# NFC-Attendance-System.net
KiCad netlist of a schematic drawn in EAGLE
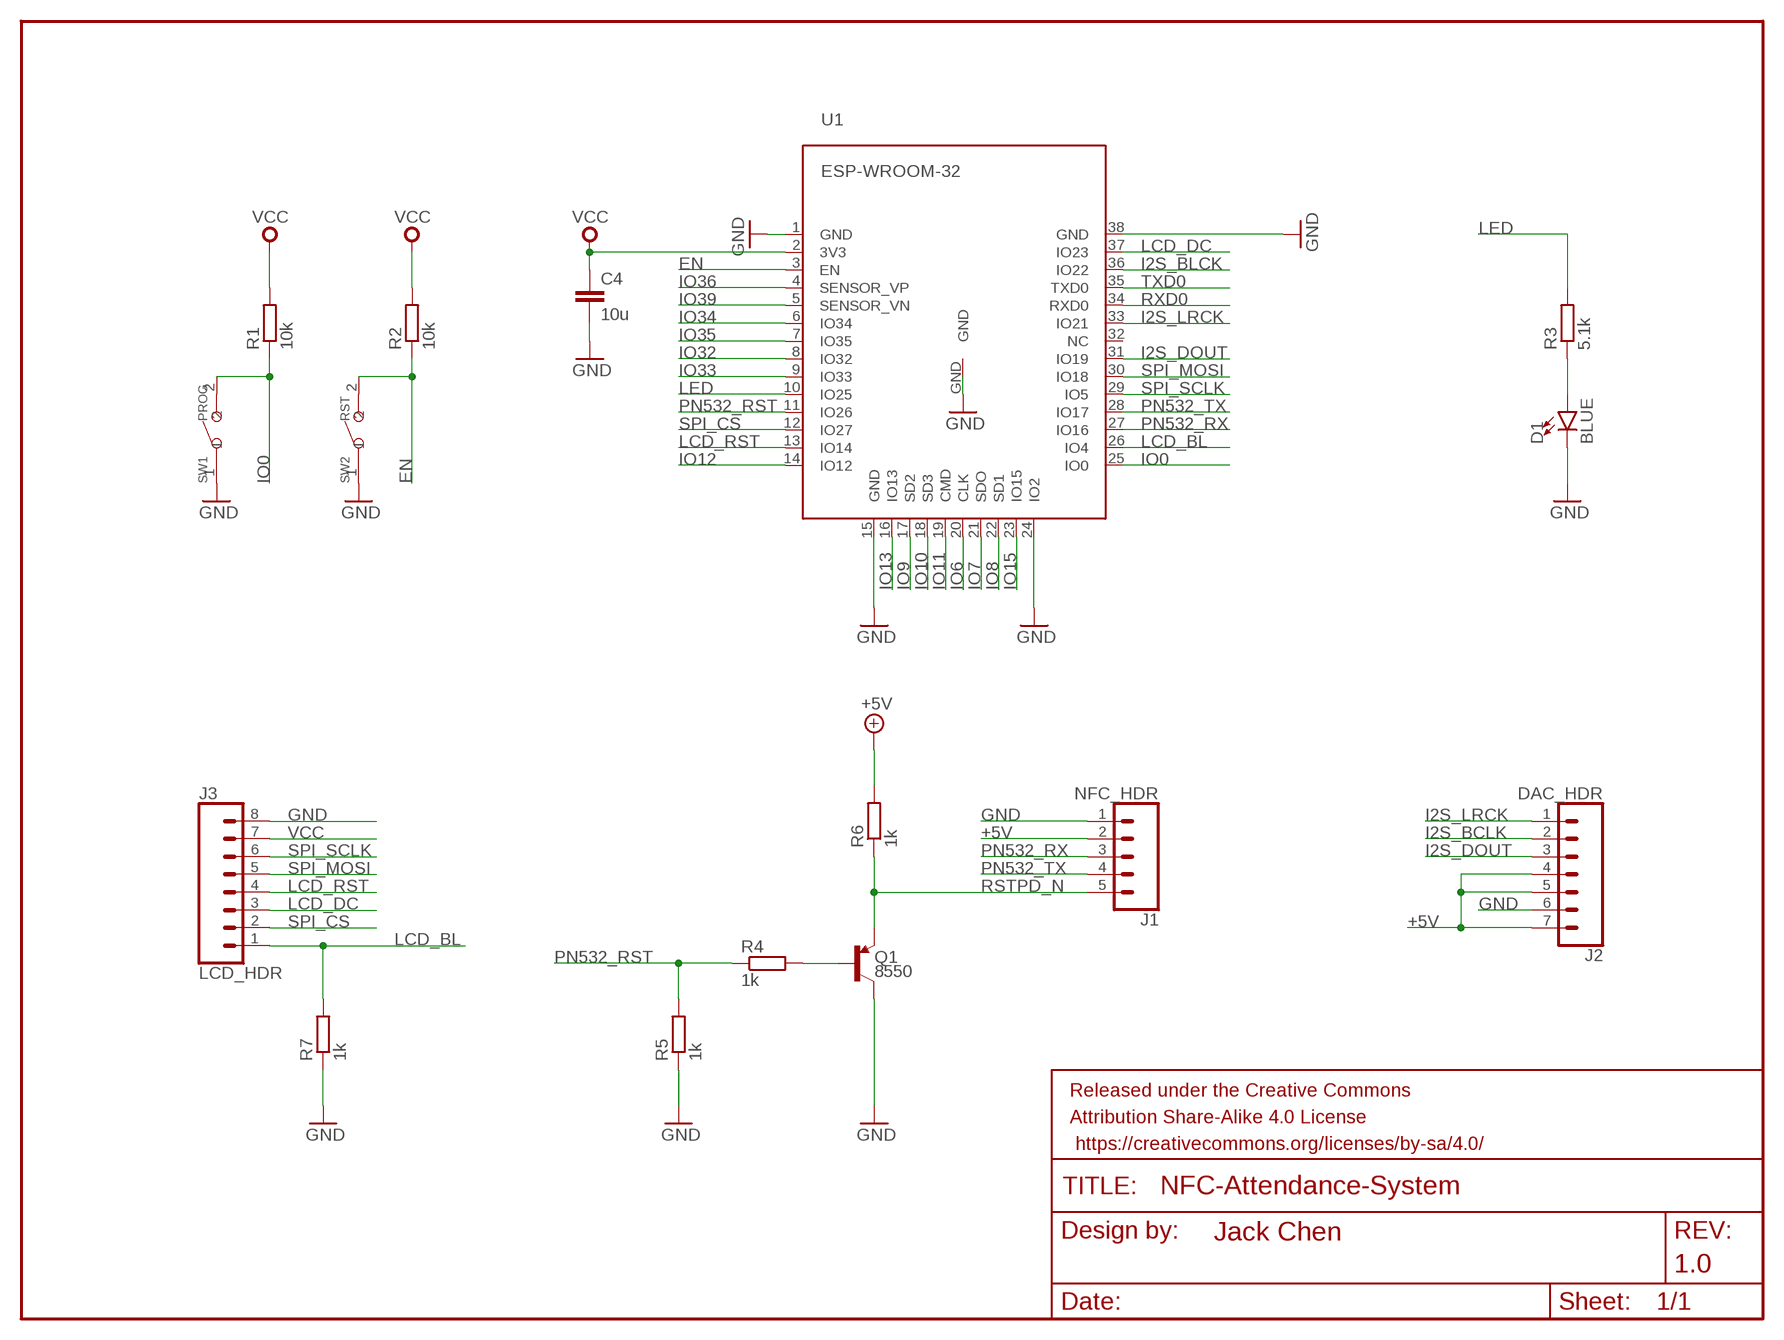
[diagram p0: schematic, sheet 1]

(export (version "E")
  (design (tool "Eeschema 10.0.6"))
  (components
    (comp (ref "C4")
      (value "10u")
      (footprint "eagle-import:C0603")
      (libsource (lib "eagle-import") (part "C-EUC0603"))
    )
    (comp (ref "D1")
      (value "BLUE")
      (footprint "eagle-import:LED_5MM")
      (libsource (lib "eagle-import") (part "LED5MM"))
    )
    (comp (ref "FRAME1")
      (value "FRAME-LETTER")
      (footprint "eagle-import:CREATIVE_COMMONS")
      (fields (field (name "DESIGNER") "Jack Chen") (field (name "REV") "1.0"))
      (libsource (lib "eagle-import") (part "FRAME-LETTER"))
    )
    (comp (ref "J1")
      (value "NFC_HDR")
      (footprint "eagle-import:1X05")
      (libsource (lib "eagle-import") (part "CONN_05"))
    )
    (comp (ref "J2")
      (value "DAC_HDR")
      (footprint "eagle-import:1X07")
      (libsource (lib "eagle-import") (part "CONN_07"))
    )
    (comp (ref "J3")
      (value "LCD_HDR")
      (footprint "eagle-import:1X08")
      (libsource (lib "eagle-import") (part "CONN_08{dblquote}"))
    )
    (comp (ref "Q1")
      (value "8550")
      (footprint "eagle-import:SOT23-3")
      (libsource (lib "eagle-import") (part "TRANS_PNP-MMBT4403"))
    )
    (comp (ref "R1")
      (value "10k")
      (footprint "eagle-import:R0603")
      (libsource (lib "eagle-import") (part "R-EU_R0603"))
    )
    (comp (ref "R2")
      (value "10k")
      (footprint "eagle-import:R0603")
      (libsource (lib "eagle-import") (part "R-EU_R0603"))
    )
    (comp (ref "R3")
      (value "5.1k")
      (footprint "eagle-import:R0603")
      (libsource (lib "eagle-import") (part "R-EU_R0603"))
    )
    (comp (ref "R4")
      (value "1k")
      (footprint "eagle-import:R0603")
      (libsource (lib "eagle-import") (part "R-EU_R0603"))
    )
    (comp (ref "R5")
      (value "1k")
      (footprint "eagle-import:R0603")
      (libsource (lib "eagle-import") (part "R-EU_R0603"))
    )
    (comp (ref "R6")
      (value "1k")
      (footprint "eagle-import:R0603")
      (libsource (lib "eagle-import") (part "R-EU_R0603"))
    )
    (comp (ref "R7")
      (value "1k")
      (footprint "eagle-import:R0603")
      (libsource (lib "eagle-import") (part "R-EU_R0603"))
    )
    (comp (ref "SW1")
      (value "PROG")
      (footprint "eagle-import:SW2-4.0-6.0X3.0X2.5MM")
      (libsource (lib "eagle-import") (part "SMD-BUTTON(2P-6.0X3.0X2.5MM)-DHT-1163S"))
    )
    (comp (ref "SW2")
      (value "RST")
      (footprint "eagle-import:SW2-4.0-6.0X3.0X2.5MM")
      (libsource (lib "eagle-import") (part "SMD-BUTTON(2P-6.0X3.0X2.5MM)-DHT-1163S"))
    )
    (comp (ref "U1")
      (value "ESP-WROOM-32")
      (footprint "eagle-import:ESP-WROOM-32")
      (libsource (lib "eagle-import") (part "ESP-WROOM-32"))
    )
  )
  (nets
    (net (code "1") (name "+5V") (class "Default")
      (node (ref "J1") (pin "2") (pinfunction "2_2") (pintype "passive"))
      (node (ref "J2") (pin "4") (pinfunction "4_4") (pintype "passive"))
      (node (ref "J2") (pin "5") (pinfunction "5_5") (pintype "passive"))
      (node (ref "J2") (pin "7") (pinfunction "7_7") (pintype "passive"))
      (node (ref "R6") (pin "2") (pinfunction "2_2") (pintype "passive"))
    )
    (net (code "2") (name "/EN") (class "Default")
      (node (ref "R2") (pin "1") (pinfunction "1_1") (pintype "passive"))
      (node (ref "SW2") (pin "2") (pinfunction "2_2") (pintype "bidirectional"))
      (node (ref "U1") (pin "3") (pinfunction "EN_3") (pintype "bidirectional"))
    )
    (net (code "3") (name "/I2S_BCLK") (class "Default")
      (node (ref "J2") (pin "2") (pinfunction "2_2") (pintype "passive"))
    )
    (net (code "4") (name "/I2S_BLCK") (class "Default")
      (node (ref "U1") (pin "36") (pinfunction "IO22_36") (pintype "bidirectional"))
    )
    (net (code "5") (name "/I2S_DOUT") (class "Default")
      (node (ref "J2") (pin "3") (pinfunction "3_3") (pintype "passive"))
      (node (ref "U1") (pin "31") (pinfunction "IO19_31") (pintype "bidirectional"))
    )
    (net (code "6") (name "/I2S_LRCK") (class "Default")
      (node (ref "J2") (pin "1") (pinfunction "1_1") (pintype "passive"))
      (node (ref "U1") (pin "33") (pinfunction "IO21_33") (pintype "bidirectional"))
    )
    (net (code "7") (name "/IO0") (class "Default")
      (node (ref "R1") (pin "1") (pinfunction "1_1") (pintype "passive"))
      (node (ref "SW1") (pin "2") (pinfunction "2_2") (pintype "bidirectional"))
      (node (ref "U1") (pin "25") (pinfunction "IO0_25") (pintype "bidirectional"))
    )
    (net (code "8") (name "/IO6") (class "Default")
      (node (ref "U1") (pin "20") (pinfunction "CLK_20") (pintype "bidirectional"))
    )
    (net (code "9") (name "/IO7") (class "Default")
      (node (ref "U1") (pin "21") (pinfunction "SDO_21") (pintype "bidirectional"))
    )
    (net (code "10") (name "/IO8") (class "Default")
      (node (ref "U1") (pin "22") (pinfunction "SD1_22") (pintype "bidirectional"))
    )
    (net (code "11") (name "/IO9") (class "Default")
      (node (ref "U1") (pin "17") (pinfunction "SD2_17") (pintype "bidirectional"))
    )
    (net (code "12") (name "/IO10") (class "Default")
      (node (ref "U1") (pin "18") (pinfunction "SD3_18") (pintype "bidirectional"))
    )
    (net (code "13") (name "/IO11") (class "Default")
      (node (ref "U1") (pin "19") (pinfunction "CMD_19") (pintype "bidirectional"))
    )
    (net (code "14") (name "/IO12") (class "Default")
      (node (ref "U1") (pin "14") (pinfunction "IO12_14") (pintype "bidirectional"))
    )
    (net (code "15") (name "/IO13") (class "Default")
      (node (ref "U1") (pin "16") (pinfunction "IO13_16") (pintype "bidirectional"))
    )
    (net (code "16") (name "/IO15") (class "Default")
      (node (ref "U1") (pin "23") (pinfunction "IO15_23") (pintype "bidirectional"))
    )
    (net (code "17") (name "/IO32") (class "Default")
      (node (ref "U1") (pin "8") (pinfunction "IO32_8") (pintype "bidirectional"))
    )
    (net (code "18") (name "/IO33") (class "Default")
      (node (ref "U1") (pin "9") (pinfunction "IO33_9") (pintype "bidirectional"))
    )
    (net (code "19") (name "/IO34") (class "Default")
      (node (ref "U1") (pin "6") (pinfunction "IO34_6") (pintype "bidirectional"))
    )
    (net (code "20") (name "/IO35") (class "Default")
      (node (ref "U1") (pin "7") (pinfunction "IO35_7") (pintype "bidirectional"))
    )
    (net (code "21") (name "/IO36") (class "Default")
      (node (ref "U1") (pin "4") (pinfunction "SENSOR_VP_4") (pintype "bidirectional"))
    )
    (net (code "22") (name "/IO39") (class "Default")
      (node (ref "U1") (pin "5") (pinfunction "SENSOR_VN_5") (pintype "bidirectional"))
    )
    (net (code "23") (name "/LCD_BL") (class "Default")
      (node (ref "J3") (pin "1") (pinfunction "1_1") (pintype "passive"))
      (node (ref "R7") (pin "2") (pinfunction "2_2") (pintype "passive"))
      (node (ref "U1") (pin "26") (pinfunction "IO4_26") (pintype "bidirectional"))
    )
    (net (code "24") (name "/LCD_DC") (class "Default")
      (node (ref "J3") (pin "3") (pinfunction "3_3") (pintype "passive"))
      (node (ref "U1") (pin "37") (pinfunction "IO23_37") (pintype "bidirectional"))
    )
    (net (code "25") (name "/LCD_RST") (class "Default")
      (node (ref "J3") (pin "4") (pinfunction "4_4") (pintype "passive"))
      (node (ref "U1") (pin "13") (pinfunction "IO14_13") (pintype "bidirectional"))
    )
    (net (code "26") (name "/LED") (class "Default")
      (node (ref "R3") (pin "2") (pinfunction "2_2") (pintype "passive"))
      (node (ref "U1") (pin "10") (pinfunction "IO25_10") (pintype "bidirectional"))
    )
    (net (code "27") (name "/PN532_RST") (class "Default")
      (node (ref "R4") (pin "1") (pinfunction "1_1") (pintype "passive"))
      (node (ref "R5") (pin "2") (pinfunction "2_2") (pintype "passive"))
      (node (ref "U1") (pin "11") (pinfunction "IO26_11") (pintype "bidirectional"))
    )
    (net (code "28") (name "/PN532_RX") (class "Default")
      (node (ref "J1") (pin "3") (pinfunction "3_3") (pintype "passive"))
      (node (ref "U1") (pin "27") (pinfunction "IO16_27") (pintype "bidirectional"))
    )
    (net (code "29") (name "/PN532_TX") (class "Default")
      (node (ref "J1") (pin "4") (pinfunction "4_4") (pintype "passive"))
      (node (ref "U1") (pin "28") (pinfunction "IO17_28") (pintype "bidirectional"))
    )
    (net (code "30") (name "/RSTPD_N") (class "Default")
      (node (ref "J1") (pin "5") (pinfunction "5_5") (pintype "passive"))
      (node (ref "Q1") (pin "2") (pinfunction "E_2") (pintype "passive"))
      (node (ref "R6") (pin "1") (pinfunction "1_1") (pintype "passive"))
    )
    (net (code "31") (name "/RXD0") (class "Default")
      (node (ref "U1") (pin "34") (pinfunction "RXD0_34") (pintype "bidirectional"))
    )
    (net (code "32") (name "/SPI_CS") (class "Default")
      (node (ref "J3") (pin "2") (pinfunction "2_2") (pintype "passive"))
      (node (ref "U1") (pin "12") (pinfunction "IO27_12") (pintype "bidirectional"))
    )
    (net (code "33") (name "/SPI_MOSI") (class "Default")
      (node (ref "J3") (pin "5") (pinfunction "5_5") (pintype "passive"))
      (node (ref "U1") (pin "30") (pinfunction "IO18_30") (pintype "bidirectional"))
    )
    (net (code "34") (name "/SPI_SCLK") (class "Default")
      (node (ref "J3") (pin "6") (pinfunction "6_6") (pintype "passive"))
      (node (ref "U1") (pin "29") (pinfunction "IO5_29") (pintype "bidirectional"))
    )
    (net (code "35") (name "/TXD0") (class "Default")
      (node (ref "U1") (pin "35") (pinfunction "TXD0_35") (pintype "bidirectional"))
    )
    (net (code "36") (name "GND") (class "Default")
      (node (ref "C4") (pin "2") (pinfunction "2_2") (pintype "passive"))
      (node (ref "D1") (pin "K") (pinfunction "C_K") (pintype "passive"))
      (node (ref "J1") (pin "1") (pinfunction "1_1") (pintype "passive"))
      (node (ref "J2") (pin "6") (pinfunction "6_6") (pintype "passive"))
      (node (ref "J3") (pin "8") (pinfunction "8_8") (pintype "passive"))
      (node (ref "Q1") (pin "3") (pinfunction "C_3") (pintype "passive"))
      (node (ref "R5") (pin "1") (pinfunction "1_1") (pintype "passive"))
      (node (ref "R7") (pin "1") (pinfunction "1_1") (pintype "passive"))
      (node (ref "SW1") (pin "1") (pinfunction "1_1") (pintype "bidirectional"))
      (node (ref "SW2") (pin "1") (pinfunction "1_1") (pintype "bidirectional"))
      (node (ref "U1") (pin "1") (pinfunction "GND_1") (pintype "bidirectional"))
      (node (ref "U1") (pin "15") (pinfunction "GND_15") (pintype "bidirectional"))
      (node (ref "U1") (pin "24") (pinfunction "IO2_24") (pintype "bidirectional"))
      (node (ref "U1") (pin "38") (pinfunction "GND_38") (pintype "bidirectional"))
      (node (ref "U1") (pin "GND") (pinfunction "GND_GND") (pintype "bidirectional"))
    )
    (net (code "37") (name "Net-(D1-PadA)") (class "Default")
      (node (ref "D1") (pin "A") (pinfunction "A_A") (pintype "passive"))
      (node (ref "R3") (pin "1") (pinfunction "1_1") (pintype "passive"))
    )
    (net (code "38") (name "Net-(Q1-B)") (class "Default")
      (node (ref "Q1") (pin "1") (pinfunction "B_1") (pintype "passive"))
      (node (ref "R4") (pin "2") (pinfunction "2_2") (pintype "passive"))
    )
    (net (code "39") (name "VCC") (class "Default")
      (node (ref "C4") (pin "1") (pinfunction "1_1") (pintype "passive"))
      (node (ref "J3") (pin "7") (pinfunction "7_7") (pintype "passive"))
      (node (ref "R1") (pin "2") (pinfunction "2_2") (pintype "passive"))
      (node (ref "R2") (pin "2") (pinfunction "2_2") (pintype "passive"))
      (node (ref "U1") (pin "2") (pinfunction "3V3_2") (pintype "bidirectional"))
    )
    (net (code "40") (name "unconnected-(U1-NC-Pad32)") (class "Default")
      (node (ref "U1") (pin "32") (pinfunction "NC_32") (pintype "bidirectional"))
    )
  )
)
